# Host_Bypass_FPGA_1V2.net
KiCad netlist of a schematic drawn in Altium Designer
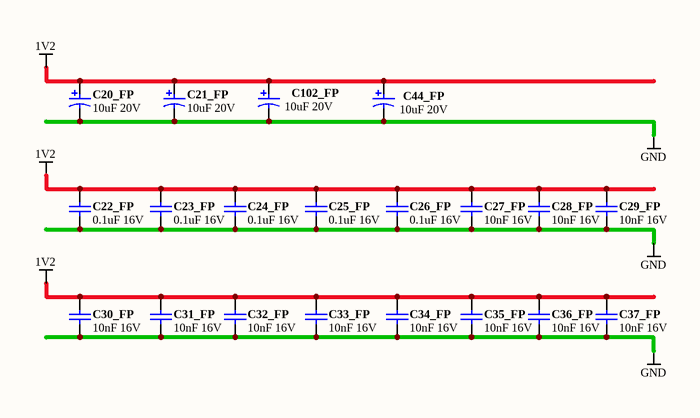
[diagram p0: Host_Bypass_FPGA_1V2.SchDoc]

(export (version "E")
  (design (tool "Eeschema 10.0.6"))
  (components
    (comp (ref "C20_FP")
      (value "10uF 20V")
      (footprint "CAPC3528-STAR")
      (description "Capacitor, Tantalum, 10uF 10% 20V MCCT-B (3528)")
      (fields (field (name "TOLERANCE") "10 %"))
      (libsource (lib "altium-import") (part "root_0_CAP-P_"))
    )
    (comp (ref "C21_FP")
      (value "10uF 20V")
      (footprint "CAPC3528-STAR")
      (description "Capacitor, Tantalum, 10uF 10% 20V MCCT-B (3528)")
      (fields (field (name "TOLERANCE") "10 %"))
      (libsource (lib "altium-import") (part "root_0_CAP-P_"))
    )
    (comp (ref "C22_FP")
      (value "0.1uF 16V")
      (footprint "CAPC1005-STAR")
      (description "Capacitor, Ceramic, 0.1uF 10% 16V 0402 (1005) X7R")
      (fields (field (name "TOLERANCE") "10 %"))
      (libsource (lib "altium-import") (part "root_0_mirrored_CAP-NP_"))
    )
    (comp (ref "C23_FP")
      (value "0.1uF 16V")
      (footprint "CAPC1005-STAR")
      (description "Capacitor, Ceramic, 0.1uF 10% 16V 0402 (1005) X7R")
      (fields (field (name "TOLERANCE") "10 %"))
      (libsource (lib "altium-import") (part "root_0_mirrored_CAP-NP_"))
    )
    (comp (ref "C24_FP")
      (value "0.1uF 16V")
      (footprint "CAPC1005-STAR")
      (description "Capacitor, Ceramic, 0.1uF 10% 16V 0402 (1005) X7R")
      (fields (field (name "TOLERANCE") "10 %"))
      (libsource (lib "altium-import") (part "root_0_mirrored_CAP-NP_"))
    )
    (comp (ref "C25_FP")
      (value "0.1uF 16V")
      (footprint "CAPC1005-STAR")
      (description "Capacitor, Ceramic, 0.1uF 10% 16V 0402 (1005) X7R")
      (fields (field (name "TOLERANCE") "10 %"))
      (libsource (lib "altium-import") (part "root_0_mirrored_CAP-NP_"))
    )
    (comp (ref "C26_FP")
      (value "0.1uF 16V")
      (footprint "CAPC1005-STAR")
      (description "Capacitor, Ceramic, 0.1uF 10% 16V 0402 (1005) X7R")
      (fields (field (name "TOLERANCE") "10 %"))
      (libsource (lib "altium-import") (part "root_0_mirrored_CAP-NP_"))
    )
    (comp (ref "C27_FP")
      (value "10nF 16V")
      (footprint "CAPC1005-STAR")
      (description "Capacitor, Ceramic, 10nF 10% 16V 0402 (1005) X7R")
      (fields (field (name "TOLERANCE") "10 %"))
      (libsource (lib "altium-import") (part "root_0_CAP-NP_"))
    )
    (comp (ref "C28_FP")
      (value "10nF 16V")
      (footprint "CAPC1005-STAR")
      (description "Capacitor, Ceramic, 10nF 10% 16V 0402 (1005) X7R")
      (fields (field (name "TOLERANCE") "10 %"))
      (libsource (lib "altium-import") (part "root_0_CAP-NP_"))
    )
    (comp (ref "C29_FP")
      (value "10nF 16V")
      (footprint "CAPC1005-STAR")
      (description "Capacitor, Ceramic, 10nF 10% 16V 0402 (1005) X7R")
      (fields (field (name "TOLERANCE") "10 %"))
      (libsource (lib "altium-import") (part "root_0_CAP-NP_"))
    )
    (comp (ref "C30_FP")
      (value "10nF 16V")
      (footprint "CAPC1005-STAR")
      (description "Capacitor, Ceramic, 10nF 10% 16V 0402 (1005) X7R")
      (fields (field (name "TOLERANCE") "10 %"))
      (libsource (lib "altium-import") (part "root_0_CAP-NP_"))
    )
    (comp (ref "C31_FP")
      (value "10nF 16V")
      (footprint "CAPC1005-STAR")
      (description "Capacitor, Ceramic, 10nF 10% 16V 0402 (1005) X7R")
      (fields (field (name "TOLERANCE") "10 %"))
      (libsource (lib "altium-import") (part "root_0_CAP-NP_"))
    )
    (comp (ref "C32_FP")
      (value "10nF 16V")
      (footprint "CAPC1005-STAR")
      (description "Capacitor, Ceramic, 10nF 10% 16V 0402 (1005) X7R")
      (fields (field (name "TOLERANCE") "10 %"))
      (libsource (lib "altium-import") (part "root_0_CAP-NP_"))
    )
    (comp (ref "C33_FP")
      (value "10nF 16V")
      (footprint "CAPC1005-STAR")
      (description "Capacitor, Ceramic, 10nF 10% 16V 0402 (1005) X7R")
      (fields (field (name "TOLERANCE") "10 %"))
      (libsource (lib "altium-import") (part "root_0_CAP-NP_"))
    )
    (comp (ref "C34_FP")
      (value "10nF 16V")
      (footprint "CAPC1005-STAR")
      (description "Capacitor, Ceramic, 10nF 10% 16V 0402 (1005) X7R")
      (fields (field (name "TOLERANCE") "10 %"))
      (libsource (lib "altium-import") (part "root_0_CAP-NP_"))
    )
    (comp (ref "C35_FP")
      (value "10nF 16V")
      (footprint "CAPC1005-STAR")
      (description "Capacitor, Ceramic, 10nF 10% 16V 0402 (1005) X7R")
      (fields (field (name "TOLERANCE") "10 %"))
      (libsource (lib "altium-import") (part "root_0_CAP-NP_"))
    )
    (comp (ref "C36_FP")
      (value "10nF 16V")
      (footprint "CAPC1005-STAR")
      (description "Capacitor, Ceramic, 10nF 10% 16V 0402 (1005) X7R")
      (fields (field (name "TOLERANCE") "10 %"))
      (libsource (lib "altium-import") (part "root_0_CAP-NP_"))
    )
    (comp (ref "C37_FP")
      (value "10nF 16V")
      (footprint "CAPC1005-STAR")
      (description "Capacitor, Ceramic, 10nF 10% 16V 0402 (1005) X7R")
      (fields (field (name "TOLERANCE") "10 %"))
      (libsource (lib "altium-import") (part "root_0_CAP-NP_"))
    )
    (comp (ref "C44_FP")
      (value "10uF 20V")
      (footprint "CAPC3528-STAR")
      (description "Capacitor, Tantalum, 10uF 10% 20V MCCT-B (3528)")
      (fields (field (name "TOLERANCE") "10 %"))
      (libsource (lib "altium-import") (part "root_0_CAP-P_"))
    )
    (comp (ref "C102_FP")
      (value "10uF 20V")
      (footprint "CAPC3528-STAR")
      (description "Capacitor, Tantalum, 10uF 10% 20V MCCT-B (3528)")
      (fields (field (name "TOLERANCE") "10 %"))
      (libsource (lib "altium-import") (part "root_0_CAP-P_"))
    )
  )
  (nets
    (net (code "1") (name "1V2") (class "Default")
      (node (ref "C102_FP") (pin "1") (pinfunction "1_1") (pintype "passive"))
      (node (ref "C20_FP") (pin "1") (pinfunction "1_1") (pintype "passive"))
      (node (ref "C21_FP") (pin "1") (pinfunction "1_1") (pintype "passive"))
      (node (ref "C22_FP") (pin "1") (pinfunction "1_1") (pintype "passive"))
      (node (ref "C23_FP") (pin "1") (pinfunction "1_1") (pintype "passive"))
      (node (ref "C24_FP") (pin "1") (pinfunction "1_1") (pintype "passive"))
      (node (ref "C25_FP") (pin "1") (pinfunction "1_1") (pintype "passive"))
      (node (ref "C26_FP") (pin "1") (pinfunction "1_1") (pintype "passive"))
      (node (ref "C27_FP") (pin "1") (pinfunction "1_1") (pintype "passive"))
      (node (ref "C28_FP") (pin "1") (pinfunction "1_1") (pintype "passive"))
      (node (ref "C29_FP") (pin "1") (pinfunction "1_1") (pintype "passive"))
      (node (ref "C30_FP") (pin "1") (pinfunction "1_1") (pintype "passive"))
      (node (ref "C31_FP") (pin "1") (pinfunction "1_1") (pintype "passive"))
      (node (ref "C32_FP") (pin "1") (pinfunction "1_1") (pintype "passive"))
      (node (ref "C33_FP") (pin "1") (pinfunction "1_1") (pintype "passive"))
      (node (ref "C34_FP") (pin "1") (pinfunction "1_1") (pintype "passive"))
      (node (ref "C35_FP") (pin "1") (pinfunction "1_1") (pintype "passive"))
      (node (ref "C36_FP") (pin "1") (pinfunction "1_1") (pintype "passive"))
      (node (ref "C37_FP") (pin "1") (pinfunction "1_1") (pintype "passive"))
      (node (ref "C44_FP") (pin "1") (pinfunction "1_1") (pintype "passive"))
    )
    (net (code "2") (name "GND") (class "Default")
      (node (ref "C102_FP") (pin "2") (pinfunction "2_2") (pintype "passive"))
      (node (ref "C20_FP") (pin "2") (pinfunction "2_2") (pintype "passive"))
      (node (ref "C21_FP") (pin "2") (pinfunction "2_2") (pintype "passive"))
      (node (ref "C22_FP") (pin "2") (pinfunction "2_2") (pintype "passive"))
      (node (ref "C23_FP") (pin "2") (pinfunction "2_2") (pintype "passive"))
      (node (ref "C24_FP") (pin "2") (pinfunction "2_2") (pintype "passive"))
      (node (ref "C25_FP") (pin "2") (pinfunction "2_2") (pintype "passive"))
      (node (ref "C26_FP") (pin "2") (pinfunction "2_2") (pintype "passive"))
      (node (ref "C27_FP") (pin "2") (pinfunction "2_2") (pintype "passive"))
      (node (ref "C28_FP") (pin "2") (pinfunction "2_2") (pintype "passive"))
      (node (ref "C29_FP") (pin "2") (pinfunction "2_2") (pintype "passive"))
      (node (ref "C30_FP") (pin "2") (pinfunction "2_2") (pintype "passive"))
      (node (ref "C31_FP") (pin "2") (pinfunction "2_2") (pintype "passive"))
      (node (ref "C32_FP") (pin "2") (pinfunction "2_2") (pintype "passive"))
      (node (ref "C33_FP") (pin "2") (pinfunction "2_2") (pintype "passive"))
      (node (ref "C34_FP") (pin "2") (pinfunction "2_2") (pintype "passive"))
      (node (ref "C35_FP") (pin "2") (pinfunction "2_2") (pintype "passive"))
      (node (ref "C36_FP") (pin "2") (pinfunction "2_2") (pintype "passive"))
      (node (ref "C37_FP") (pin "2") (pinfunction "2_2") (pintype "passive"))
      (node (ref "C44_FP") (pin "2") (pinfunction "2_2") (pintype "passive"))
    )
  )
)
